# DSPComm.net
KiCad netlist of a schematic drawn in Altium Designer
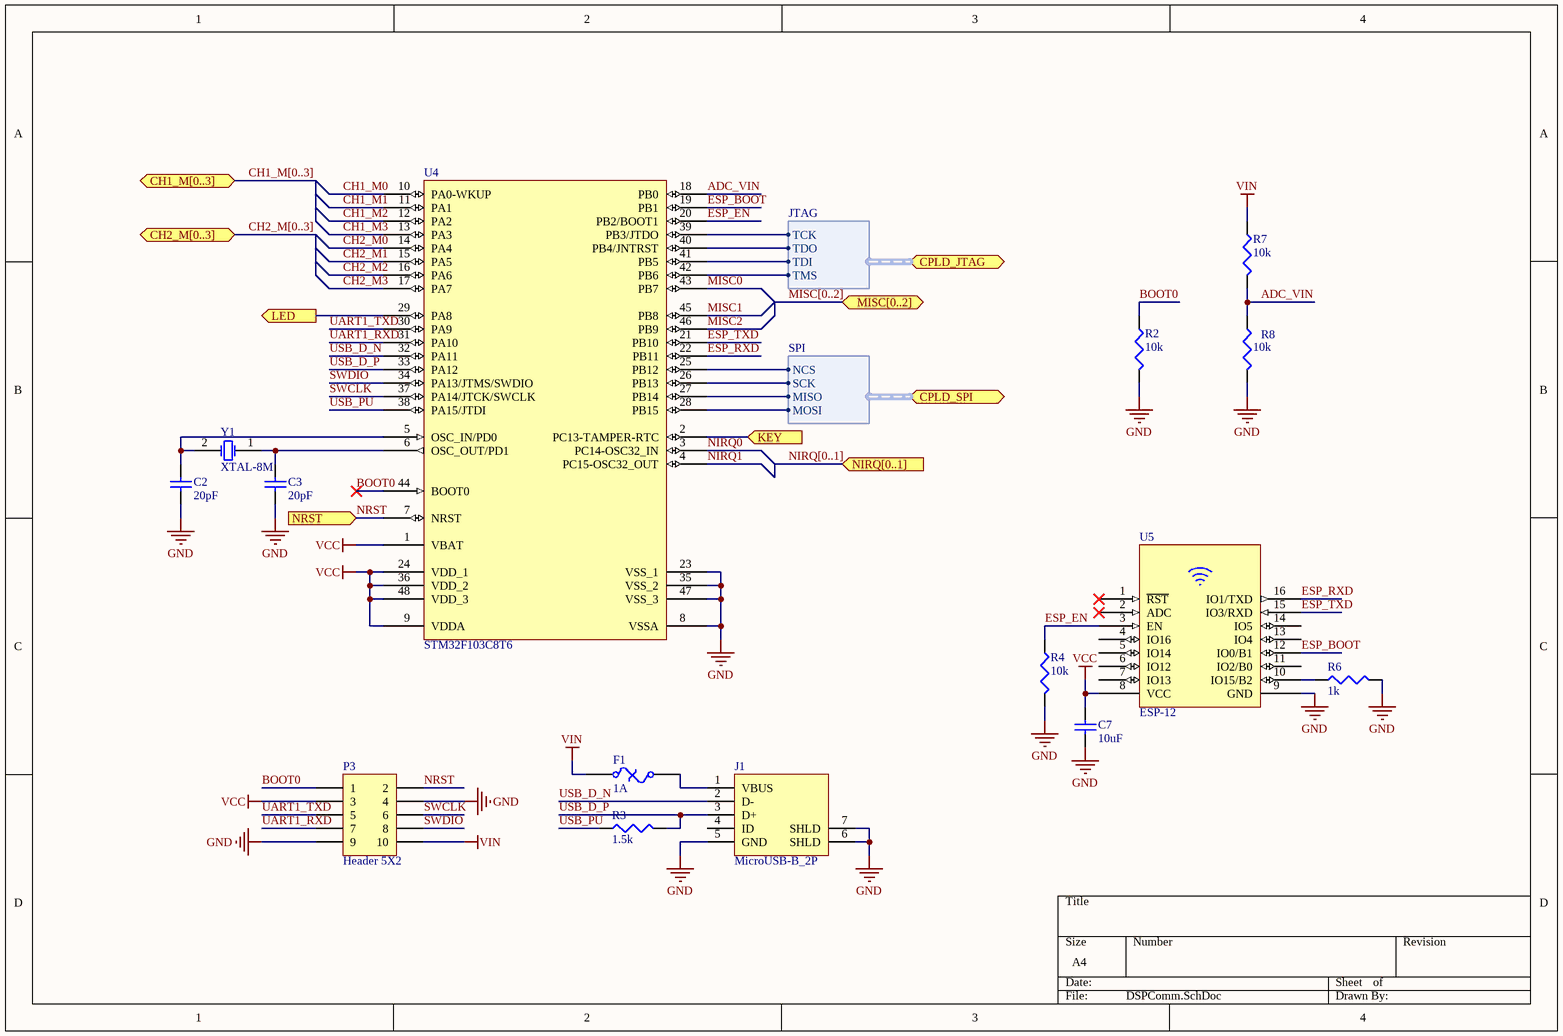
[diagram p0: DSPComm.SchDoc]

(export (version "E")
  (design (tool "Eeschema 10.0.6"))
  (components
    (comp (ref "C2")
      (value "20pF")
      (footprint "0603C")
      (description "Capacitor")
      (fields (field (name "Comment") "Cap") (field (name "PUBLISHER") "Altium Limited"))
      (libsource (lib "Miscellaneous Devices") (part "Cap"))
    )
    (comp (ref "C3")
      (value "20pF")
      (footprint "0603C")
      (description "Capacitor")
      (fields (field (name "Comment") "Cap") (field (name "PUBLISHER") "Altium Limited"))
      (libsource (lib "Miscellaneous Devices") (part "Cap"))
    )
    (comp (ref "C7")
      (value "10uF")
      (footprint "0805C")
      (description "Capacitor")
      (fields (field (name "Comment") "Cap") (field (name "PUBLISHER") "Altium Limited"))
      (libsource (lib "Miscellaneous Devices") (part "Cap"))
    )
    (comp (ref "F1")
      (value "1A")
      (footprint "1206F")
      (description "Thermal Fuse")
      (fields (field (name "PUBLISHER") "Altium Limited"))
      (libsource (lib "Miscellaneous Devices") (part "Fuse Thermal"))
    )
    (comp (ref "J1")
      (value "MicroUSB-B_2P")
      (footprint "MICRO-USB-B-2P")
      (description "MicroUSB母座")
      (libsource (lib "WiDSO") (part "MicroUSB-B_2P"))
    )
    (comp (ref "P3")
      (value "Header 5X2")
      (footprint "HDR2X5")
      (description "Header, 5-Pin, Dual row")
      (fields (field (name "PUBLISHER") "Altium Limited"))
      (libsource (lib "Miscellaneous Connectors") (part "Header 5X2"))
    )
    (comp (ref "R2")
      (value "10k")
      (footprint "0603R")
      (description "Resistor")
      (fields (field (name "Comment") "Res3") (field (name "PUBLISHER") "Altium Limited"))
      (libsource (lib "Miscellaneous Devices") (part "Res3"))
    )
    (comp (ref "R3")
      (value "1.5k")
      (footprint "0603R")
      (description "Resistor")
      (fields (field (name "Comment") "Res3") (field (name "PUBLISHER") "Altium Limited"))
      (libsource (lib "Miscellaneous Devices") (part "Res3"))
    )
    (comp (ref "R4")
      (value "10k")
      (footprint "0603R")
      (description "Resistor")
      (fields (field (name "Comment") "Res3") (field (name "PUBLISHER") "Altium Limited"))
      (libsource (lib "Miscellaneous Devices") (part "Res3"))
    )
    (comp (ref "R6")
      (value "1k")
      (footprint "0603R")
      (description "Resistor")
      (fields (field (name "Comment") "Res3") (field (name "PUBLISHER") "Altium Limited"))
      (libsource (lib "Miscellaneous Devices") (part "Res3"))
    )
    (comp (ref "R7")
      (value "10k")
      (footprint "0603R")
      (description "Resistor")
      (fields (field (name "Comment") "Res3") (field (name "PUBLISHER") "Altium Limited"))
      (libsource (lib "Miscellaneous Devices") (part "Res3"))
    )
    (comp (ref "R8")
      (value "10k")
      (footprint "0603R")
      (description "Resistor")
      (fields (field (name "Comment") "Res3") (field (name "PUBLISHER") "Altium Limited"))
      (libsource (lib "Miscellaneous Devices") (part "Res3"))
    )
    (comp (ref "U4")
      (value "STM32F103C8T6")
      (footprint "LQFP48_M")
      (description "STM32 ARM-based 32-bit MCU with 64 Kbytes Flash, 48-pin LQFP, Industrial Temperature")
      (fields (field (name "PUBLISHER") "Altium Limited"))
      (libsource (lib "ST Microcontroller 32-Bit STM32") (part "STM32F103C8T6"))
    )
    (comp (ref "U5")
      (value "ESP-12")
      (footprint "ESP-12")
      (description "串口Wifi模块")
      (libsource (lib "WiDSO") (part "ESP-12"))
    )
    (comp (ref "Y1")
      (value "XTAL-8M")
      (footprint "XTAL_5032_2P")
      (description "Crystal Oscillator")
      (fields (field (name "PUBLISHER") "Altium Limited"))
      (libsource (lib "Miscellaneous Devices") (part "XTAL"))
    )
  )
  (nets
    (net (code "3") (name "/ADC_VIN") (class "Default")
      (node (ref "R7") (pin "2") (pinfunction "2_2") (pintype "passive"))
      (node (ref "R8") (pin "1") (pinfunction "1_1") (pintype "passive"))
      (node (ref "U4") (pin "18") (pinfunction "PB0_18") (pintype "bidirectional"))
    )
    (net (code "4") (name "/BOOT0") (class "Default")
      (node (ref "P3") (pin "1") (pinfunction "1_1") (pintype "passive"))
      (node (ref "R2") (pin "1") (pinfunction "1_1") (pintype "passive"))
      (node (ref "U4") (pin "44") (pinfunction "BOOT0_44") (pintype "input"))
    )
    (net (code "5") (name "/CH1_M0") (class "Default")
      (node (ref "U4") (pin "10") (pinfunction "PA0-WKUP_10") (pintype "bidirectional"))
    )
    (net (code "6") (name "/CH1_M1") (class "Default")
      (node (ref "U4") (pin "11") (pinfunction "PA1_11") (pintype "bidirectional"))
    )
    (net (code "7") (name "/CH1_M2") (class "Default")
      (node (ref "U4") (pin "12") (pinfunction "PA2_12") (pintype "bidirectional"))
    )
    (net (code "8") (name "/CH1_M3") (class "Default")
      (node (ref "U4") (pin "13") (pinfunction "PA3_13") (pintype "bidirectional"))
    )
    (net (code "10") (name "/CH2_M0") (class "Default")
      (node (ref "U4") (pin "14") (pinfunction "PA4_14") (pintype "bidirectional"))
    )
    (net (code "11") (name "/CH2_M1") (class "Default")
      (node (ref "U4") (pin "15") (pinfunction "PA5_15") (pintype "bidirectional"))
    )
    (net (code "12") (name "/CH2_M2") (class "Default")
      (node (ref "U4") (pin "16") (pinfunction "PA6_16") (pintype "bidirectional"))
    )
    (net (code "13") (name "/CH2_M3") (class "Default")
      (node (ref "U4") (pin "17") (pinfunction "PA7_17") (pintype "bidirectional"))
    )
    (net (code "15") (name "/ESP_BOOT") (class "Default")
      (node (ref "U4") (pin "19") (pinfunction "PB1_19") (pintype "bidirectional"))
      (node (ref "U5") (pin "12") (pinfunction "IO0/B1_12") (pintype "bidirectional"))
    )
    (net (code "16") (name "/ESP_EN") (class "Default")
      (node (ref "R4") (pin "1") (pinfunction "1_1") (pintype "passive"))
      (node (ref "U4") (pin "20") (pinfunction "PB2/BOOT1_20") (pintype "bidirectional"))
      (node (ref "U5") (pin "3") (pinfunction "EN_3") (pintype "input"))
    )
    (net (code "17") (name "/ESP_RXD") (class "Default")
      (node (ref "U4") (pin "22") (pinfunction "PB11_22") (pintype "bidirectional"))
      (node (ref "U5") (pin "16") (pinfunction "IO1/TXD_16") (pintype "output"))
    )
    (net (code "18") (name "/ESP_TXD") (class "Default")
      (node (ref "U4") (pin "21") (pinfunction "PB10_21") (pintype "bidirectional"))
      (node (ref "U5") (pin "15") (pinfunction "IO3/RXD_15") (pintype "input"))
    )
    (net (code "19") (name "/KEY") (class "Default")
      (node (ref "U4") (pin "2") (pinfunction "PC13-TAMPER-RTC_2") (pintype "bidirectional"))
    )
    (net (code "20") (name "/LED") (class "Default")
      (node (ref "U4") (pin "29") (pinfunction "PA8_29") (pintype "bidirectional"))
    )
    (net (code "21") (name "/MISC0") (class "Default")
      (node (ref "U4") (pin "43") (pinfunction "PB7_43") (pintype "bidirectional"))
    )
    (net (code "22") (name "/MISC1") (class "Default")
      (node (ref "U4") (pin "45") (pinfunction "PB8_45") (pintype "bidirectional"))
    )
    (net (code "23") (name "/MISC2") (class "Default")
      (node (ref "U4") (pin "46") (pinfunction "PB9_46") (pintype "bidirectional"))
    )
    (net (code "25") (name "/MISO") (class "Default")
      (node (ref "U4") (pin "27") (pinfunction "PB14_27") (pintype "bidirectional"))
    )
    (net (code "26") (name "/MOSI") (class "Default")
      (node (ref "U4") (pin "28") (pinfunction "PB15_28") (pintype "bidirectional"))
    )
    (net (code "27") (name "/NCS") (class "Default")
      (node (ref "U4") (pin "25") (pinfunction "PB12_25") (pintype "bidirectional"))
    )
    (net (code "28") (name "/NIRQ0") (class "Default")
      (node (ref "U4") (pin "3") (pinfunction "PC14-OSC32_IN_3") (pintype "bidirectional"))
    )
    (net (code "29") (name "/NIRQ1") (class "Default")
      (node (ref "U4") (pin "4") (pinfunction "PC15-OSC32_OUT_4") (pintype "bidirectional"))
    )
    (net (code "31") (name "/NRST") (class "Default")
      (node (ref "P3") (pin "2") (pinfunction "2_2") (pintype "passive"))
      (node (ref "U4") (pin "7") (pinfunction "NRST_7") (pintype "bidirectional"))
    )
    (net (code "32") (name "/SCK") (class "Default")
      (node (ref "U4") (pin "26") (pinfunction "PB13_26") (pintype "bidirectional"))
    )
    (net (code "33") (name "/SWCLK") (class "Default")
      (node (ref "P3") (pin "6") (pinfunction "6_6") (pintype "passive"))
      (node (ref "U4") (pin "37") (pinfunction "PA14/JTCK/SWCLK_37") (pintype "bidirectional"))
    )
    (net (code "34") (name "/SWDIO") (class "Default")
      (node (ref "P3") (pin "8") (pinfunction "8_8") (pintype "passive"))
      (node (ref "U4") (pin "34") (pinfunction "PA13/JTMS/SWDIO_34") (pintype "bidirectional"))
    )
    (net (code "35") (name "/TCK") (class "Default")
      (node (ref "U4") (pin "39") (pinfunction "PB3/JTDO_39") (pintype "bidirectional"))
    )
    (net (code "36") (name "/TDI") (class "Default")
      (node (ref "U4") (pin "41") (pinfunction "PB5_41") (pintype "bidirectional"))
    )
    (net (code "37") (name "/TDO") (class "Default")
      (node (ref "U4") (pin "40") (pinfunction "PB4/JNTRST_40") (pintype "bidirectional"))
    )
    (net (code "38") (name "/TMS") (class "Default")
      (node (ref "U4") (pin "42") (pinfunction "PB6_42") (pintype "bidirectional"))
    )
    (net (code "39") (name "/UART1_RXD") (class "Default")
      (node (ref "P3") (pin "7") (pinfunction "7_7") (pintype "passive"))
      (node (ref "U4") (pin "31") (pinfunction "PA10_31") (pintype "bidirectional"))
    )
    (net (code "40") (name "/UART1_TXD") (class "Default")
      (node (ref "P3") (pin "5") (pinfunction "5_5") (pintype "passive"))
      (node (ref "U4") (pin "30") (pinfunction "PA9_30") (pintype "bidirectional"))
    )
    (net (code "41") (name "/USB_D_N") (class "Default")
      (node (ref "J1") (pin "2") (pinfunction "D-_2") (pintype "passive"))
      (node (ref "U4") (pin "32") (pinfunction "PA11_32") (pintype "bidirectional"))
    )
    (net (code "42") (name "/USB_D_P") (class "Default")
      (node (ref "J1") (pin "3") (pinfunction "D+_3") (pintype "passive"))
      (node (ref "R3") (pin "2") (pinfunction "2_2") (pintype "passive"))
      (node (ref "U4") (pin "33") (pinfunction "PA12_33") (pintype "bidirectional"))
    )
    (net (code "43") (name "/USB_PU") (class "Default")
      (node (ref "R3") (pin "1") (pinfunction "1_1") (pintype "passive"))
      (node (ref "U4") (pin "38") (pinfunction "PA15/JTDI_38") (pintype "bidirectional"))
    )
    (net (code "46") (name "GND") (class "Default")
      (node (ref "C2") (pin "1") (pinfunction "1_1") (pintype "passive"))
      (node (ref "C3") (pin "1") (pinfunction "1_1") (pintype "passive"))
      (node (ref "C7") (pin "2") (pinfunction "2_2") (pintype "passive"))
      (node (ref "J1") (pin "5") (pinfunction "GND_5") (pintype "power_in"))
      (node (ref "J1") (pin "6") (pinfunction "SHLD_6") (pintype "passive"))
      (node (ref "J1") (pin "7") (pinfunction "SHLD_7") (pintype "passive"))
      (node (ref "P3") (pin "4") (pinfunction "4_4") (pintype "passive"))
      (node (ref "P3") (pin "9") (pinfunction "9_9") (pintype "passive"))
      (node (ref "R2") (pin "2") (pinfunction "2_2") (pintype "passive"))
      (node (ref "R4") (pin "2") (pinfunction "2_2") (pintype "passive"))
      (node (ref "R6") (pin "2") (pinfunction "2_2") (pintype "passive"))
      (node (ref "R8") (pin "2") (pinfunction "2_2") (pintype "passive"))
      (node (ref "U4") (pin "23") (pinfunction "VSS_1_23") (pintype "power_in"))
      (node (ref "U4") (pin "35") (pinfunction "VSS_2_35") (pintype "power_in"))
      (node (ref "U4") (pin "47") (pinfunction "VSS_3_47") (pintype "power_in"))
      (node (ref "U4") (pin "8") (pinfunction "VSSA_8") (pintype "power_in"))
      (node (ref "U5") (pin "9") (pinfunction "GND_9") (pintype "power_in"))
    )
    (net (code "47") (name "Net-(J1-VBUS)") (class "Default")
      (node (ref "F1") (pin "2") (pinfunction "2_2") (pintype "passive"))
      (node (ref "J1") (pin "1") (pinfunction "VBUS_1") (pintype "power_in"))
    )
    (net (code "48") (name "Net-(U4-OSC_IN{slash}PD0)") (class "Default")
      (node (ref "C2") (pin "2") (pinfunction "2_2") (pintype "passive"))
      (node (ref "U4") (pin "5") (pinfunction "OSC_IN/PD0_5") (pintype "input"))
      (node (ref "Y1") (pin "2") (pinfunction "OSC2_2") (pintype "passive"))
    )
    (net (code "49") (name "Net-(U4-OSC_OUT{slash}PD1)") (class "Default")
      (node (ref "C3") (pin "2") (pinfunction "2_2") (pintype "passive"))
      (node (ref "U4") (pin "6") (pinfunction "OSC_OUT/PD1_6") (pintype "output"))
      (node (ref "Y1") (pin "1") (pinfunction "OSC1_1") (pintype "passive"))
    )
    (net (code "50") (name "Net-(U5-IO15{slash}B2)") (class "Default")
      (node (ref "R6") (pin "1") (pinfunction "1_1") (pintype "passive"))
      (node (ref "U5") (pin "10") (pinfunction "IO15/B2_10") (pintype "bidirectional"))
    )
    (net (code "51") (name "VCC") (class "Default")
      (node (ref "C7") (pin "1") (pinfunction "1_1") (pintype "passive"))
      (node (ref "P3") (pin "3") (pinfunction "3_3") (pintype "passive"))
      (node (ref "U4") (pin "1") (pinfunction "VBAT_1") (pintype "power_in"))
      (node (ref "U4") (pin "24") (pinfunction "VDD_1_24") (pintype "power_in"))
      (node (ref "U4") (pin "36") (pinfunction "VDD_2_36") (pintype "power_in"))
      (node (ref "U4") (pin "48") (pinfunction "VDD_3_48") (pintype "power_in"))
      (node (ref "U4") (pin "9") (pinfunction "VDDA_9") (pintype "power_in"))
      (node (ref "U5") (pin "8") (pinfunction "VCC_8") (pintype "passive"))
    )
    (net (code "52") (name "VIN") (class "Default")
      (node (ref "F1") (pin "1") (pinfunction "1_1") (pintype "passive"))
      (node (ref "P3") (pin "10") (pinfunction "10_10") (pintype "passive"))
      (node (ref "R7") (pin "1") (pinfunction "1_1") (pintype "passive"))
    )
    (net (code "53") (name "unconnected-(J1-ID-Pad4)") (class "Default")
      (node (ref "J1") (pin "4") (pinfunction "ID_4") (pintype "passive"))
    )
    (net (code "54") (name "unconnected-(U5-ADC-Pad2)") (class "Default")
      (node (ref "U5") (pin "2") (pinfunction "ADC_2") (pintype "input+no_connect"))
    )
    (net (code "55") (name "unconnected-(U5-IO2{slash}B0-Pad11)") (class "Default")
      (node (ref "U5") (pin "11") (pinfunction "IO2/B0_11") (pintype "bidirectional"))
    )
    (net (code "56") (name "unconnected-(U5-IO4-Pad13)") (class "Default")
      (node (ref "U5") (pin "13") (pinfunction "IO4_13") (pintype "bidirectional"))
    )
    (net (code "57") (name "unconnected-(U5-IO5-Pad14)") (class "Default")
      (node (ref "U5") (pin "14") (pinfunction "IO5_14") (pintype "bidirectional"))
    )
    (net (code "58") (name "unconnected-(U5-IO12-Pad6)") (class "Default")
      (node (ref "U5") (pin "6") (pinfunction "IO12_6") (pintype "bidirectional"))
    )
    (net (code "59") (name "unconnected-(U5-IO13-Pad7)") (class "Default")
      (node (ref "U5") (pin "7") (pinfunction "IO13_7") (pintype "bidirectional"))
    )
    (net (code "60") (name "unconnected-(U5-IO14-Pad5)") (class "Default")
      (node (ref "U5") (pin "5") (pinfunction "IO14_5") (pintype "bidirectional"))
    )
    (net (code "61") (name "unconnected-(U5-IO16-Pad4)") (class "Default")
      (node (ref "U5") (pin "4") (pinfunction "IO16_4") (pintype "bidirectional"))
    )
    (net (code "62") (name "unconnected-(U5-~{RST}-Pad1)") (class "Default")
      (node (ref "U5") (pin "1") (pinfunction "~{RST}_1") (pintype "input+no_connect"))
    )
  )
)
